# SCH_airPi_2024-02-11.net
KiCad netlist of a schematic drawn in EasyEDA
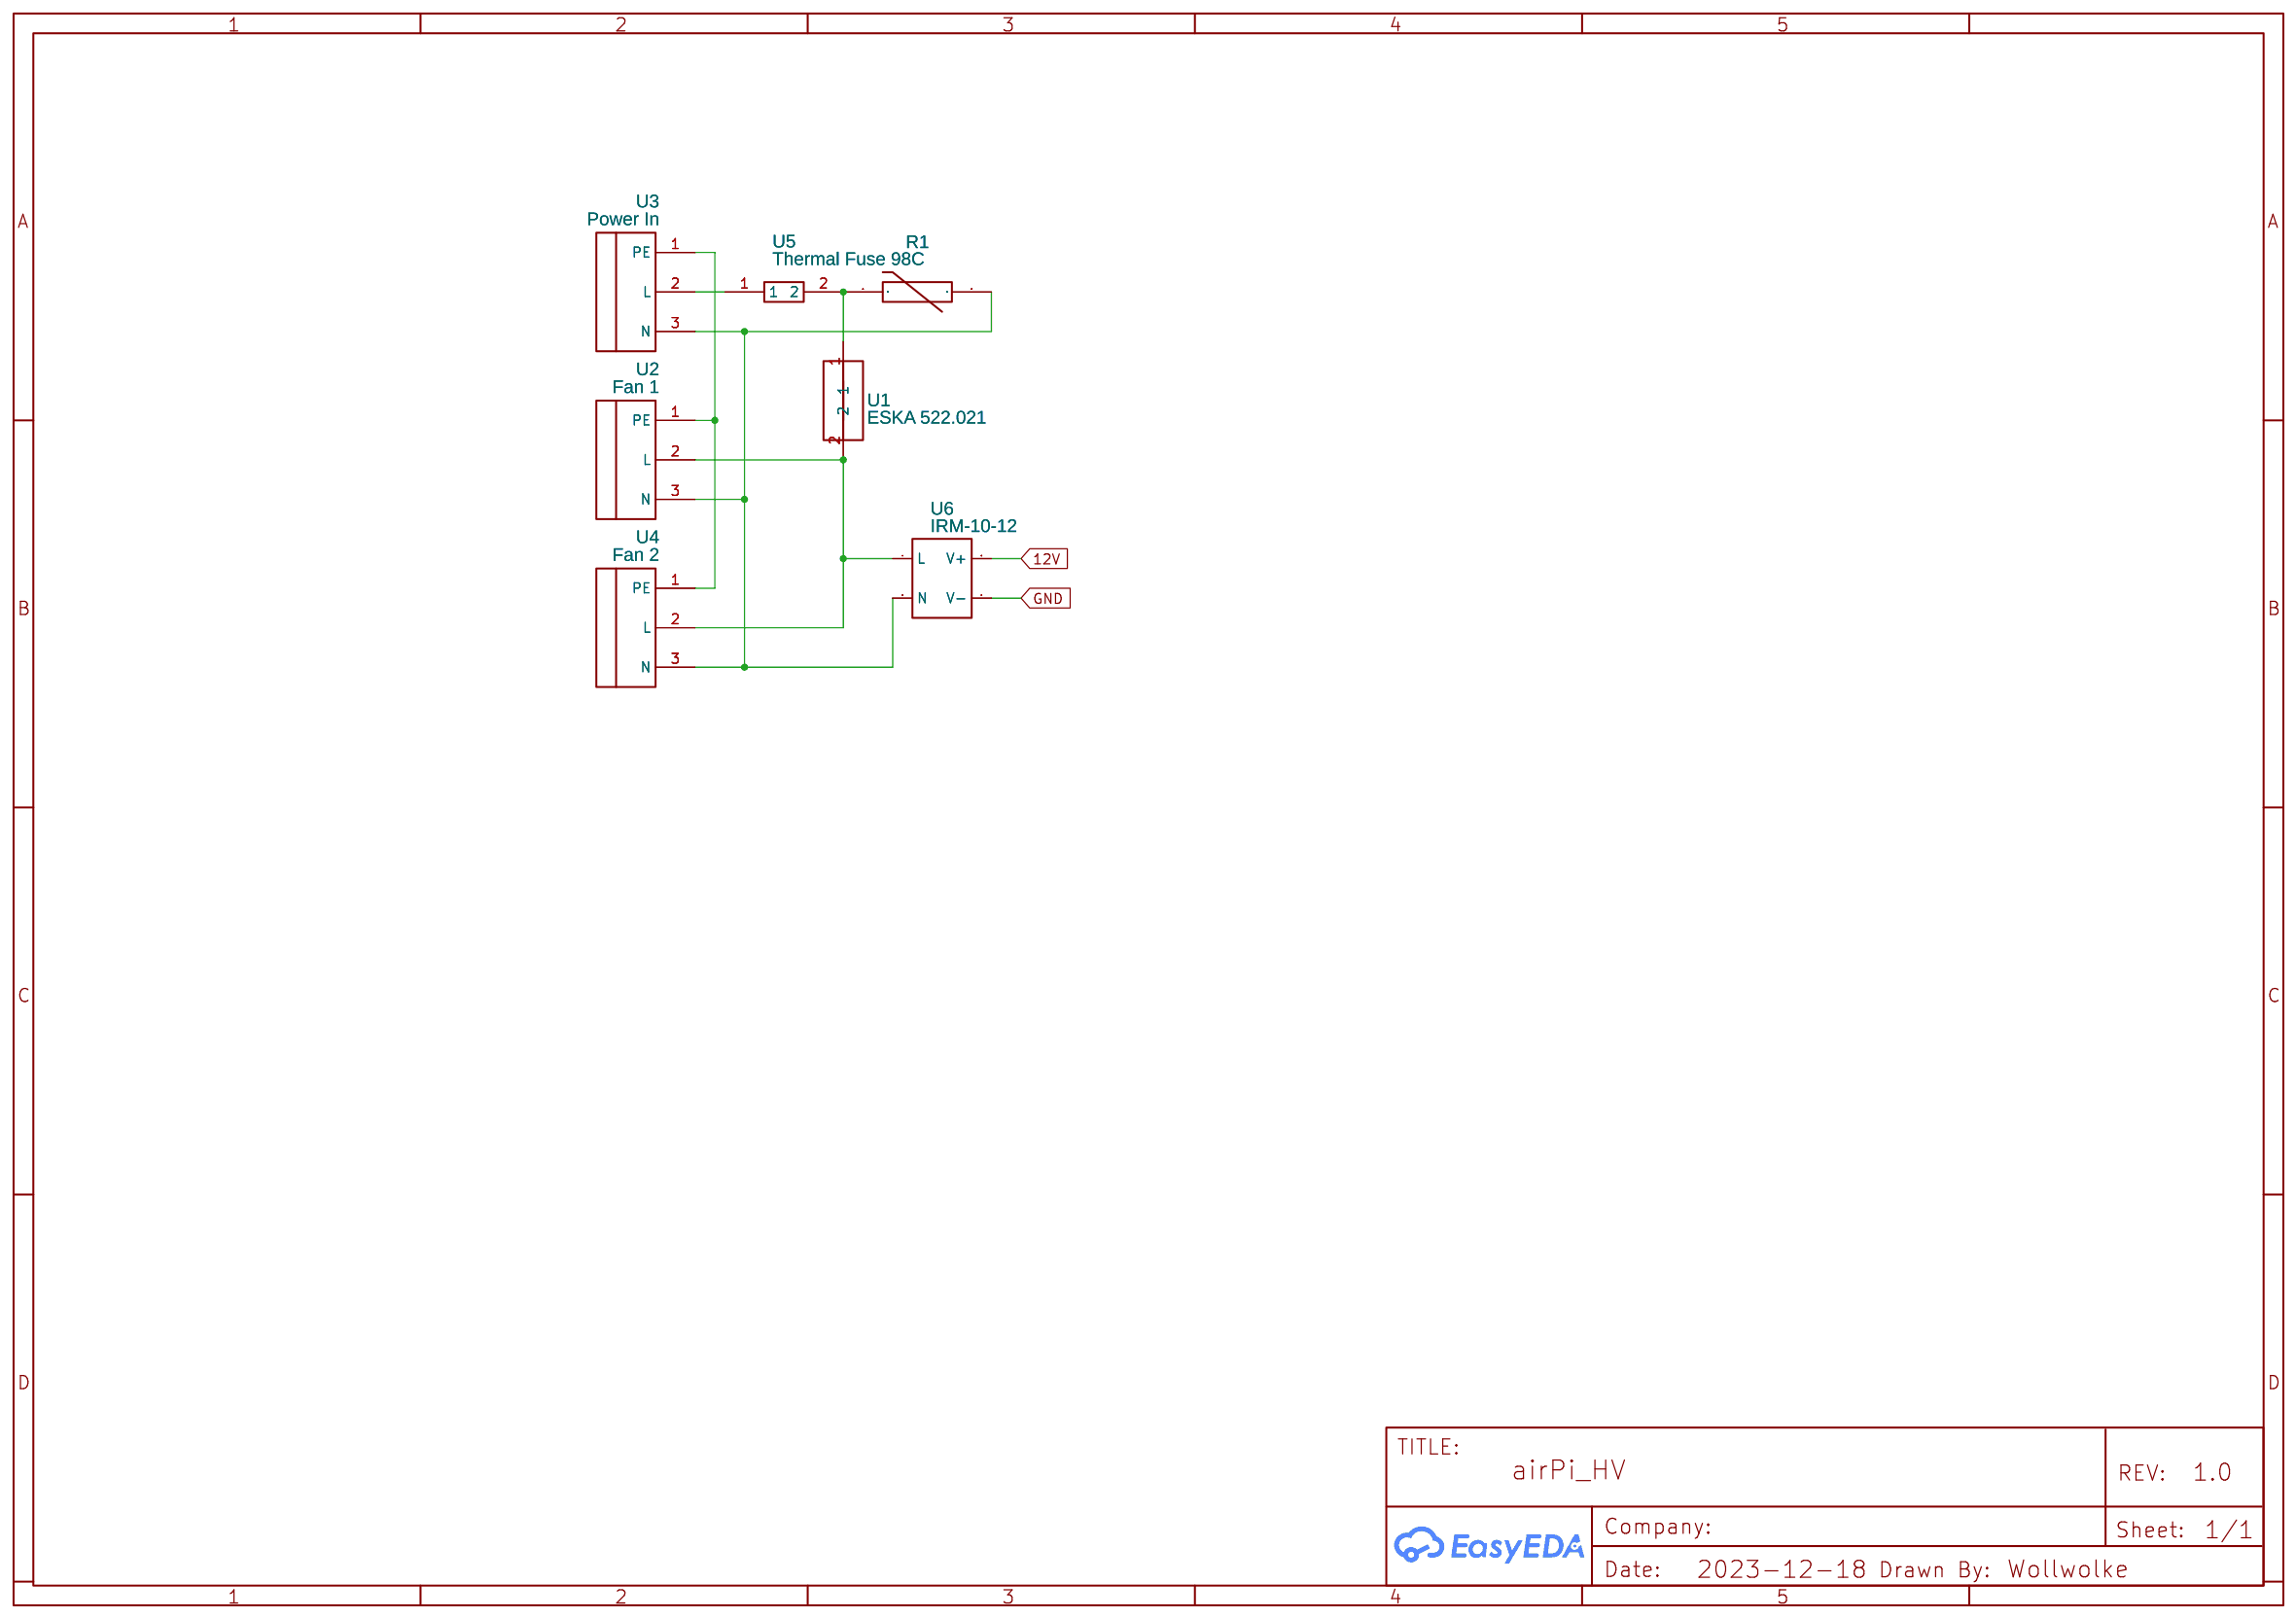
[diagram p0: airPi_HV]
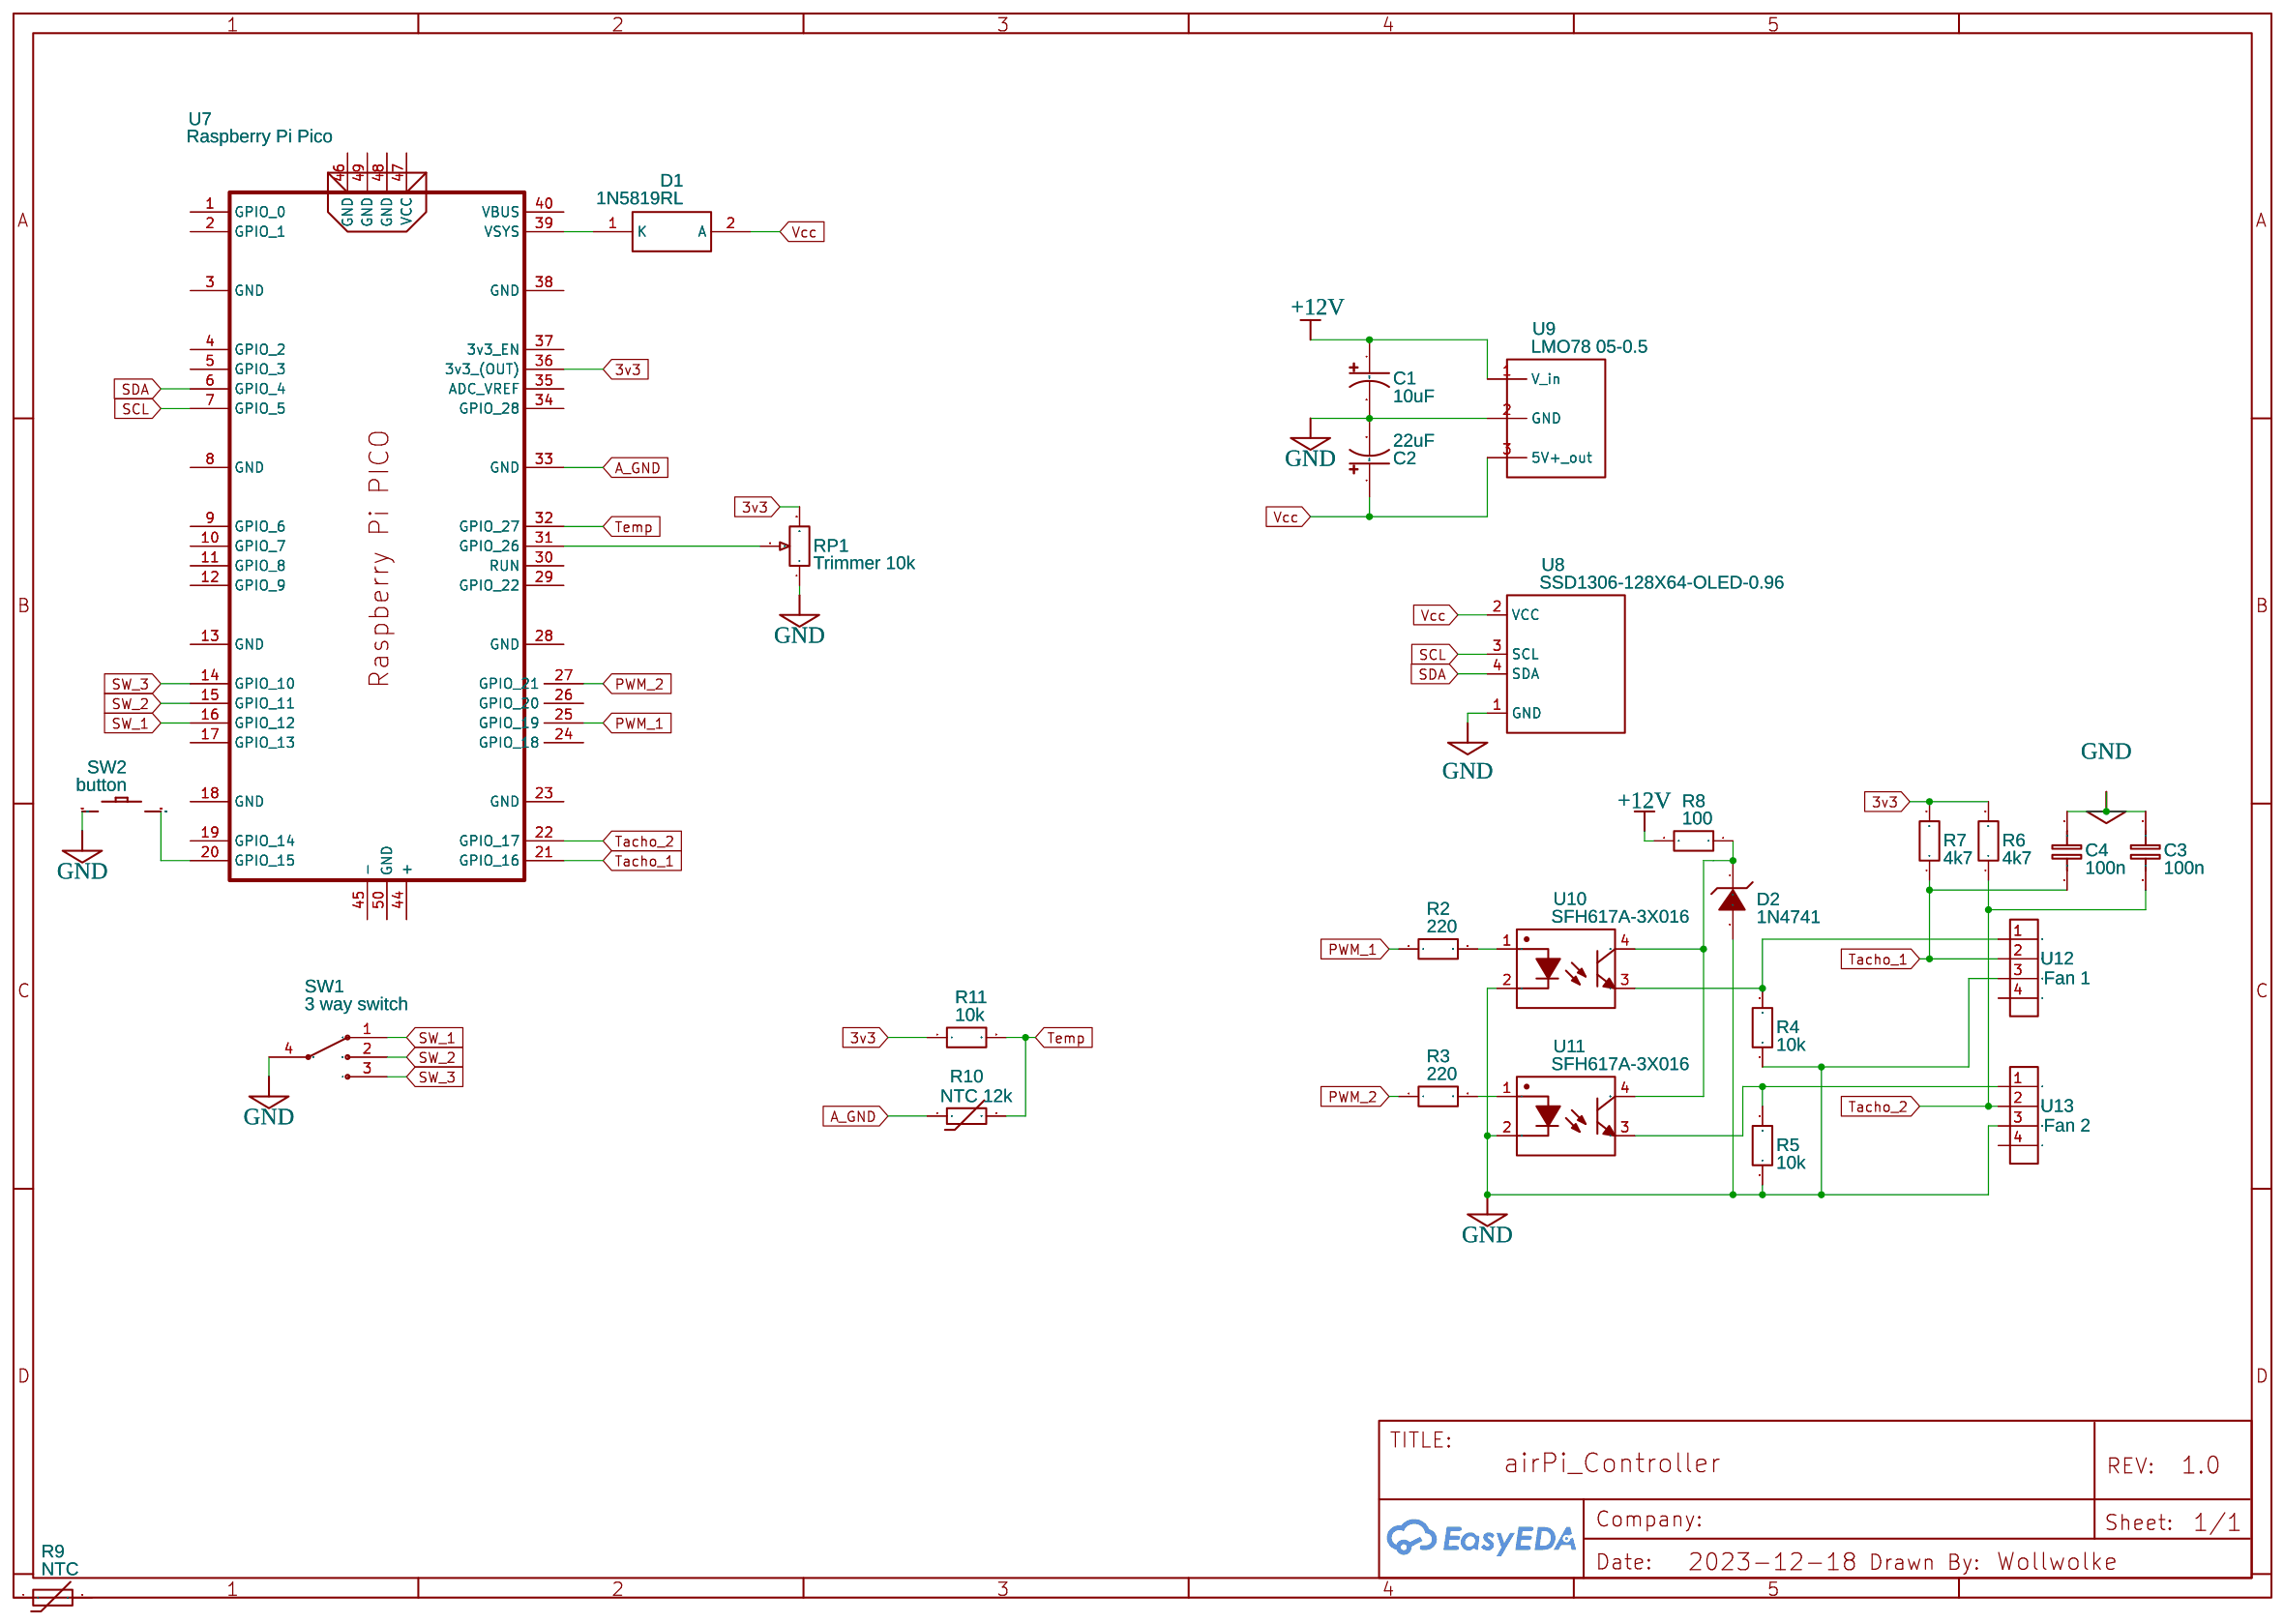
[diagram p1: airPi_Controller]

(export (version "E")
  (design (tool "Eeschema 10.0.6"))
  (components
    (comp (ref "R1")
      (value "Varistor")
      (fields
        (field (name "Manufacturer Part") "B72220S0301K101")
        (field (name "Manufacturer") "EPCOS - TDK Electronics")
      )
      (libsource (lib "") (part "B72220S0301K551"))
    )
    (comp (ref "U1")
      (value "ESKA 522.021")
      (fields (field (name "Manufacturer Part") "2050000172717"))
      (libsource (lib "") (part "ESKA 380"))
    )
    (comp (ref "U2")
      (value "Fan 1")
      (fields
        (field (name "Manufacturer Part") "MSTBA 2,5/ 3-G-5,08")
        (field (name "Manufacturer") "Phoenix Contact(菲尼克斯)")
      )
      (libsource (lib "") (part "MSTBA 2,5/ 3-G-5,08"))
    )
    (comp (ref "U3")
      (value "Power In")
      (fields
        (field (name "Manufacturer Part") "MSTBA 2,5/ 3-G-5,08")
        (field (name "Manufacturer") "Phoenix Contact(菲尼克斯)")
      )
      (libsource (lib "") (part "MSTBA 2,5/ 3-G-5,08"))
    )
    (comp (ref "U4")
      (value "Fan 2")
      (fields
        (field (name "Manufacturer Part") "MSTBA 2,5/ 3-G-5,08")
        (field (name "Manufacturer") "Phoenix Contact(菲尼克斯)")
      )
      (libsource (lib "") (part "MSTBA 2,5/ 3-G-5,08"))
    )
    (comp (ref "U5")
      (value "Thermal Fuse 98C")
      (fields (field (name "Manufacturer Part") "777.098") (field (name "Manufacturer") "ESKA"))
      (libsource (lib "") (part "Thermal Fuse ESKA"))
    )
    (comp (ref "U6")
      (value "IRM-10-12")
      (fields (field (name "Manufacturer") "MEAN WELL USA Inc."))
      (libsource (lib "") (part "IRM-10-12"))
    )
    (comp (ref "C1") (value "10uF") (libsource (lib "") (part "TANTALE-10µF")))
    (comp (ref "C2") (value "22uF") (libsource (lib "") (part "TANTALE-10µF_1")))
    (comp (ref "C3") (value "100n") (libsource (lib "") (part "C_0603_EU")))
    (comp (ref "C4") (value "100n") (libsource (lib "") (part "C_0603_EU")))
    (comp (ref "D1") (value "1N5819RL") (libsource (lib "") (part "1N5819RL")))
    (comp (ref "D2")
      (value "1N4741")
      (fields (field (name "Manufacturer Part") "1N4741A") (field (name "Manufacturer") "onsemi(安森美)"))
      (libsource (lib "") (part "1N4741A_C238927"))
    )
    (comp (ref "R2") (value "220") (libsource (lib "") (part "R_0603_EU_1")))
    (comp (ref "R3") (value "220") (libsource (lib "") (part "R_0603_EU_1")))
    (comp (ref "R4") (value "10k") (libsource (lib "") (part "R_0603_EU")))
    (comp (ref "R5") (value "10k") (libsource (lib "") (part "R_0603_EU")))
    (comp (ref "R6") (value "4k7") (libsource (lib "") (part "R_0603_EU")))
    (comp (ref "R7") (value "4k7") (libsource (lib "") (part "R_0603_EU")))
    (comp (ref "R8") (value "100") (libsource (lib "") (part "R_0603_EU_2")))
    (comp (ref "R9")
      (value "NTC")
      (fields (field (name "Manufacturer Part") "NTC 5D-9(弯脚)") (field (name "Manufacturer") "RUILON(瑞隆源)"))
      (libsource (lib "") (part "NTC 5D-9"))
    )
    (comp (ref "R10")
      (value "NTC 12k")
      (fields (field (name "Manufacturer Part") "NTC 5D-9(弯脚)") (field (name "Manufacturer") "RUILON(瑞隆源)"))
      (libsource (lib "") (part "NTC 5D-9"))
    )
    (comp (ref "R11") (value "10k") (libsource (lib "") (part "R_0603_EU_1")))
    (comp (ref "RP1") (value "Trimmer 10k") (libsource (lib "") (part "R_3386P_EU")))
    (comp (ref "SW1")
      (value "3 way switch")
      (fields
        (field (name "Manufacturer Part") "MSK-11027 Toggle Switches")
        (field (name "Manufacturer") "ReliaPro")
      )
      (libsource (lib "") (part "3 way switch"))
    )
    (comp (ref "SW2") (value "button") (libsource (lib "") (part "button")))
    (comp (ref "U7") (value "Raspberry Pi Pico") (libsource (lib "") (part "Raspberry Pi Pico")))
    (comp (ref "U8")
      (value "SSD1306-128X64-OLED-0.96")
      (libsource (lib "") (part "SSD1306-128X64-OLED-0.96"))
    )
    (comp (ref "U9")
      (value "LMO78 05-0.5")
      (libsource (lib "") (part "5V DC/DC Converter Gaptec LMO78 05-0.5 2,5W"))
    )
    (comp (ref "U10")
      (value "SFH617A-3X016")
      (fields (field (name "Manufacturer") "VISHAY(威世)"))
      (libsource (lib "") (part "SFH617A-3X016"))
    )
    (comp (ref "U11")
      (value "SFH617A-3X016")
      (fields (field (name "Manufacturer") "VISHAY(威世)"))
      (libsource (lib "") (part "SFH617A-3X016"))
    )
    (comp (ref "U12") (value "Fan 1") (libsource (lib "") (part "MolexMiniFit Jr 02*02")))
    (comp (ref "U13") (value "Fan 2") (libsource (lib "") (part "MolexMiniFit Jr 02*02")))
  )
  (nets
    (net (code "1") (name "+12V") (class "Default")
      (node (ref "C1") (pin "1") (pinfunction "1_1") (pintype "unspecified"))
      (node (ref "R8") (pin "2") (pinfunction "2_2") (pintype "unspecified"))
      (node (ref "U9") (pin "1") (pinfunction "V_in_1") (pintype "unspecified"))
    )
    (net (code "2") (name "3v3") (class "Default")
      (node (ref "R11") (pin "1") (pinfunction "1_1") (pintype "unspecified"))
      (node (ref "R6") (pin "2") (pinfunction "2_2") (pintype "unspecified"))
      (node (ref "R7") (pin "2") (pinfunction "2_2") (pintype "unspecified"))
      (node (ref "RP1") (pin "3") (pinfunction "3_3") (pintype "input"))
      (node (ref "U7") (pin "36") (pinfunction "3v3_(OUT)_36") (pintype "unspecified"))
    )
    (net (code "3") (name "12V") (class "Default")
      (node (ref "U6") (pin "V+") (pinfunction "V+_V+") (pintype "unspecified"))
    )
    (net (code "4") (name "A_GND") (class "Default")
      (node (ref "R10") (pin "1") (pinfunction "1_1") (pintype "input"))
      (node (ref "U7") (pin "33") (pinfunction "GND_33") (pintype "unspecified"))
    )
    (net (code "5") (name "GND") (class "Default")
      (node (ref "C1") (pin "2") (pinfunction "2_2") (pintype "unspecified"))
      (node (ref "C2") (pin "2") (pinfunction "2_2") (pintype "unspecified"))
      (node (ref "C3") (pin "2") (pinfunction "2_2") (pintype "unspecified"))
      (node (ref "C4") (pin "2") (pinfunction "2_2") (pintype "unspecified"))
      (node (ref "D2") (pin "2") (pinfunction "A_2") (pintype "unspecified"))
      (node (ref "R4") (pin "1") (pinfunction "1_1") (pintype "unspecified"))
      (node (ref "R5") (pin "1") (pinfunction "1_1") (pintype "unspecified"))
      (node (ref "RP1") (pin "1") (pinfunction "1_1") (pintype "input"))
      (node (ref "SW1") (pin "4") (pinfunction "2_4") (pintype "unspecified"))
      (node (ref "SW2") (pin "P$ACTIVE") (pinfunction "P$ACTIVE_P$ACTIVE") (pintype "unspecified"))
      (node (ref "U10") (pin "2") (pinfunction "C_2") (pintype "unspecified"))
      (node (ref "U11") (pin "2") (pinfunction "C_2") (pintype "unspecified"))
      (node (ref "U12") (pin "3") (pinfunction "3_3") (pintype "unspecified"))
      (node (ref "U13") (pin "3") (pinfunction "3_3") (pintype "unspecified"))
      (node (ref "U6") (pin "V-") (pinfunction "V-_V-") (pintype "unspecified"))
      (node (ref "U8") (pin "1") (pinfunction "GND_1") (pintype "input"))
      (node (ref "U9") (pin "2") (pinfunction "GND_2") (pintype "unspecified"))
    )
    (net (code "6") (name "Net-(D1-K)") (class "Default")
      (node (ref "D1") (pin "1") (pinfunction "K_1") (pintype "unspecified"))
      (node (ref "U7") (pin "39") (pinfunction "VSYS_39") (pintype "unspecified"))
    )
    (net (code "7") (name "Net-(D2-K)") (class "Default")
      (node (ref "D2") (pin "1") (pinfunction "K_1") (pintype "unspecified"))
      (node (ref "R8") (pin "1") (pinfunction "1_1") (pintype "unspecified"))
      (node (ref "U10") (pin "4") (pinfunction "C_4") (pintype "unspecified"))
      (node (ref "U11") (pin "4") (pinfunction "C_4") (pintype "unspecified"))
    )
    (net (code "8") (name "Net-(R1-Pad2)") (class "Default")
      (node (ref "R1") (pin "2") (pinfunction "2_2") (pintype "unspecified"))
      (node (ref "U1") (pin "1") (pinfunction "1_1") (pintype "unspecified"))
      (node (ref "U5") (pin "2") (pinfunction "2_2") (pintype "unspecified"))
    )
    (net (code "9") (name "Net-(U2-L)") (class "Default")
      (node (ref "U1") (pin "2") (pinfunction "2_2") (pintype "unspecified"))
      (node (ref "U2") (pin "2") (pinfunction "L_2") (pintype "unspecified"))
      (node (ref "U4") (pin "2") (pinfunction "L_2") (pintype "unspecified"))
      (node (ref "U6") (pin "L") (pinfunction "L_L") (pintype "unspecified"))
    )
    (net (code "10") (name "Net-(U2-N)") (class "Default")
      (node (ref "R1") (pin "1") (pinfunction "1_1") (pintype "unspecified"))
      (node (ref "U2") (pin "3") (pinfunction "N_3") (pintype "unspecified"))
      (node (ref "U3") (pin "3") (pinfunction "N_3") (pintype "unspecified"))
      (node (ref "U4") (pin "3") (pinfunction "N_3") (pintype "unspecified"))
      (node (ref "U6") (pin "N") (pinfunction "N_N") (pintype "unspecified"))
    )
    (net (code "11") (name "Net-(U2-PE)") (class "Default")
      (node (ref "U2") (pin "1") (pinfunction "PE_1") (pintype "unspecified"))
      (node (ref "U3") (pin "1") (pinfunction "PE_1") (pintype "unspecified"))
      (node (ref "U4") (pin "1") (pinfunction "PE_1") (pintype "unspecified"))
    )
    (net (code "12") (name "Net-(U3-L)") (class "Default")
      (node (ref "U3") (pin "2") (pinfunction "L_2") (pintype "unspecified"))
      (node (ref "U5") (pin "1") (pinfunction "1_1") (pintype "unspecified"))
    )
    (net (code "13") (name "Net-(U7-GPIO_15)") (class "Default")
      (node (ref "SW2") (pin "P$GND") (pinfunction "P$GND_P$GND") (pintype "unspecified"))
      (node (ref "U7") (pin "20") (pinfunction "GPIO_15_20") (pintype "unspecified"))
    )
    (net (code "14") (name "Net-(U7-GPIO_26)") (class "Default")
      (node (ref "RP1") (pin "2") (pinfunction "2_2") (pintype "input"))
      (node (ref "U7") (pin "31") (pinfunction "GPIO_26_31") (pintype "unspecified"))
    )
    (net (code "15") (name "Net-(U10-A)") (class "Default")
      (node (ref "R2") (pin "2") (pinfunction "2_2") (pintype "unspecified"))
      (node (ref "U10") (pin "1") (pinfunction "A_1") (pintype "unspecified"))
    )
    (net (code "16") (name "Net-(U10-E)") (class "Default")
      (node (ref "R4") (pin "2") (pinfunction "2_2") (pintype "unspecified"))
      (node (ref "U10") (pin "3") (pinfunction "E_3") (pintype "unspecified"))
      (node (ref "U12") (pin "1") (pinfunction "1_1") (pintype "unspecified"))
    )
    (net (code "17") (name "Net-(U11-A)") (class "Default")
      (node (ref "R3") (pin "2") (pinfunction "2_2") (pintype "unspecified"))
      (node (ref "U11") (pin "1") (pinfunction "A_1") (pintype "unspecified"))
    )
    (net (code "18") (name "Net-(U11-E)") (class "Default")
      (node (ref "R5") (pin "2") (pinfunction "2_2") (pintype "unspecified"))
      (node (ref "U11") (pin "3") (pinfunction "E_3") (pintype "unspecified"))
      (node (ref "U13") (pin "1") (pinfunction "1_1") (pintype "unspecified"))
    )
    (net (code "19") (name "PWM_1") (class "Default")
      (node (ref "R2") (pin "1") (pinfunction "1_1") (pintype "unspecified"))
      (node (ref "U7") (pin "25") (pinfunction "GPIO_19_25") (pintype "unspecified"))
    )
    (net (code "20") (name "PWM_2") (class "Default")
      (node (ref "R3") (pin "1") (pinfunction "1_1") (pintype "unspecified"))
      (node (ref "U7") (pin "27") (pinfunction "GPIO_21_27") (pintype "unspecified"))
    )
    (net (code "21") (name "SCL") (class "Default")
      (node (ref "U7") (pin "7") (pinfunction "GPIO_5_7") (pintype "unspecified"))
      (node (ref "U8") (pin "3") (pinfunction "SCL_3") (pintype "passive"))
    )
    (net (code "22") (name "SDA") (class "Default")
      (node (ref "U7") (pin "6") (pinfunction "GPIO_4_6") (pintype "unspecified"))
      (node (ref "U8") (pin "4") (pinfunction "SDA_4") (pintype "passive"))
    )
    (net (code "23") (name "SW_1") (class "Default")
      (node (ref "SW1") (pin "1") (pinfunction "1_1") (pintype "unspecified"))
      (node (ref "U7") (pin "16") (pinfunction "GPIO_12_16") (pintype "unspecified"))
    )
    (net (code "24") (name "SW_2") (class "Default")
      (node (ref "SW1") (pin "2") (pinfunction "3_2") (pintype "unspecified"))
      (node (ref "U7") (pin "15") (pinfunction "GPIO_11_15") (pintype "unspecified"))
    )
    (net (code "25") (name "SW_3") (class "Default")
      (node (ref "SW1") (pin "3") (pinfunction "4_3") (pintype "unspecified"))
      (node (ref "U7") (pin "14") (pinfunction "GPIO_10_14") (pintype "unspecified"))
    )
    (net (code "26") (name "Tacho_1") (class "Default")
      (node (ref "C4") (pin "1") (pinfunction "1_1") (pintype "unspecified"))
      (node (ref "R7") (pin "1") (pinfunction "1_1") (pintype "unspecified"))
      (node (ref "U12") (pin "2") (pinfunction "2_2") (pintype "unspecified"))
      (node (ref "U7") (pin "21") (pinfunction "GPIO_16_21") (pintype "unspecified"))
    )
    (net (code "27") (name "Tacho_2") (class "Default")
      (node (ref "C3") (pin "1") (pinfunction "1_1") (pintype "unspecified"))
      (node (ref "R6") (pin "1") (pinfunction "1_1") (pintype "unspecified"))
      (node (ref "U13") (pin "2") (pinfunction "2_2") (pintype "unspecified"))
      (node (ref "U7") (pin "22") (pinfunction "GPIO_17_22") (pintype "unspecified"))
    )
    (net (code "28") (name "Temp") (class "Default")
      (node (ref "R10") (pin "2") (pinfunction "2_2") (pintype "input"))
      (node (ref "R11") (pin "2") (pinfunction "2_2") (pintype "unspecified"))
      (node (ref "U7") (pin "32") (pinfunction "GPIO_27_32") (pintype "unspecified"))
    )
    (net (code "29") (name "Vcc") (class "Default")
      (node (ref "C2") (pin "1") (pinfunction "1_1") (pintype "unspecified"))
      (node (ref "D1") (pin "2") (pinfunction "A_2") (pintype "unspecified"))
      (node (ref "U8") (pin "2") (pinfunction "VCC_2") (pintype "input"))
      (node (ref "U9") (pin "3") (pinfunction "5V+_out_3") (pintype "unspecified"))
    )
    (net (code "30") (name "unconnected-(R9-Pad1)") (class "Default")
      (node (ref "R9") (pin "1") (pinfunction "1_1") (pintype "input"))
    )
    (net (code "31") (name "unconnected-(R9-Pad2)") (class "Default")
      (node (ref "R9") (pin "2") (pinfunction "2_2") (pintype "input"))
    )
    (net (code "32") (name "unconnected-(U7-+-Pad44)") (class "Default")
      (node (ref "U7") (pin "44") (pinfunction "+_44") (pintype "passive"))
    )
    (net (code "33") (name "unconnected-(U7---Pad45)") (class "Default")
      (node (ref "U7") (pin "45") (pinfunction "-_45") (pintype "passive"))
    )
    (net (code "34") (name "unconnected-(U7-3v3_EN-Pad37)") (class "Default")
      (node (ref "U7") (pin "37") (pinfunction "3v3_EN_37") (pintype "unspecified"))
    )
    (net (code "35") (name "unconnected-(U7-ADC_VREF-Pad35)") (class "Default")
      (node (ref "U7") (pin "35") (pinfunction "ADC_VREF_35") (pintype "unspecified"))
    )
    (net (code "36") (name "unconnected-(U7-GND-Pad3)") (class "Default")
      (node (ref "U7") (pin "3") (pinfunction "GND_3") (pintype "unspecified"))
    )
    (net (code "37") (name "unconnected-(U7-GND-Pad8)") (class "Default")
      (node (ref "U7") (pin "8") (pinfunction "GND_8") (pintype "unspecified"))
    )
    (net (code "38") (name "unconnected-(U7-GND-Pad13)") (class "Default")
      (node (ref "U7") (pin "13") (pinfunction "GND_13") (pintype "unspecified"))
    )
    (net (code "39") (name "unconnected-(U7-GND-Pad18)") (class "Default")
      (node (ref "U7") (pin "18") (pinfunction "GND_18") (pintype "unspecified"))
    )
    (net (code "40") (name "unconnected-(U7-GND-Pad23)") (class "Default")
      (node (ref "U7") (pin "23") (pinfunction "GND_23") (pintype "unspecified"))
    )
    (net (code "41") (name "unconnected-(U7-GND-Pad28)") (class "Default")
      (node (ref "U7") (pin "28") (pinfunction "GND_28") (pintype "unspecified"))
    )
    (net (code "42") (name "unconnected-(U7-GND-Pad38)") (class "Default")
      (node (ref "U7") (pin "38") (pinfunction "GND_38") (pintype "unspecified"))
    )
    (net (code "43") (name "unconnected-(U7-GND-Pad46)") (class "Default")
      (node (ref "U7") (pin "46") (pinfunction "GND_46") (pintype "unspecified"))
    )
    (net (code "44") (name "unconnected-(U7-GND-Pad48)") (class "Default")
      (node (ref "U7") (pin "48") (pinfunction "GND_48") (pintype "unspecified"))
    )
    (net (code "45") (name "unconnected-(U7-GND-Pad49)") (class "Default")
      (node (ref "U7") (pin "49") (pinfunction "GND_49") (pintype "unspecified"))
    )
    (net (code "46") (name "unconnected-(U7-GND-Pad50)") (class "Default")
      (node (ref "U7") (pin "50") (pinfunction "GND_50") (pintype "unspecified"))
    )
    (net (code "47") (name "unconnected-(U7-GPIO_0-Pad1)") (class "Default")
      (node (ref "U7") (pin "1") (pinfunction "GPIO_0_1") (pintype "unspecified"))
    )
    (net (code "48") (name "unconnected-(U7-GPIO_1-Pad2)") (class "Default")
      (node (ref "U7") (pin "2") (pinfunction "GPIO_1_2") (pintype "unspecified"))
    )
    (net (code "49") (name "unconnected-(U7-GPIO_2-Pad4)") (class "Default")
      (node (ref "U7") (pin "4") (pinfunction "GPIO_2_4") (pintype "unspecified"))
    )
    (net (code "50") (name "unconnected-(U7-GPIO_3-Pad5)") (class "Default")
      (node (ref "U7") (pin "5") (pinfunction "GPIO_3_5") (pintype "unspecified"))
    )
    (net (code "51") (name "unconnected-(U7-GPIO_6-Pad9)") (class "Default")
      (node (ref "U7") (pin "9") (pinfunction "GPIO_6_9") (pintype "unspecified"))
    )
    (net (code "52") (name "unconnected-(U7-GPIO_7-Pad10)") (class "Default")
      (node (ref "U7") (pin "10") (pinfunction "GPIO_7_10") (pintype "unspecified"))
    )
    (net (code "53") (name "unconnected-(U7-GPIO_8-Pad11)") (class "Default")
      (node (ref "U7") (pin "11") (pinfunction "GPIO_8_11") (pintype "unspecified"))
    )
    (net (code "54") (name "unconnected-(U7-GPIO_9-Pad12)") (class "Default")
      (node (ref "U7") (pin "12") (pinfunction "GPIO_9_12") (pintype "unspecified"))
    )
    (net (code "55") (name "unconnected-(U7-GPIO_13-Pad17)") (class "Default")
      (node (ref "U7") (pin "17") (pinfunction "GPIO_13_17") (pintype "unspecified"))
    )
    (net (code "56") (name "unconnected-(U7-GPIO_14-Pad19)") (class "Default")
      (node (ref "U7") (pin "19") (pinfunction "GPIO_14_19") (pintype "unspecified"))
    )
    (net (code "57") (name "unconnected-(U7-GPIO_18-Pad24)") (class "Default")
      (node (ref "U7") (pin "24") (pinfunction "GPIO_18_24") (pintype "unspecified"))
    )
    (net (code "58") (name "unconnected-(U7-GPIO_20-Pad26)") (class "Default")
      (node (ref "U7") (pin "26") (pinfunction "GPIO_20_26") (pintype "unspecified"))
    )
    (net (code "59") (name "unconnected-(U7-GPIO_22-Pad29)") (class "Default")
      (node (ref "U7") (pin "29") (pinfunction "GPIO_22_29") (pintype "unspecified"))
    )
    (net (code "60") (name "unconnected-(U7-GPIO_28-Pad34)") (class "Default")
      (node (ref "U7") (pin "34") (pinfunction "GPIO_28_34") (pintype "unspecified"))
    )
    (net (code "61") (name "unconnected-(U7-RUN-Pad30)") (class "Default")
      (node (ref "U7") (pin "30") (pinfunction "RUN_30") (pintype "unspecified"))
    )
    (net (code "62") (name "unconnected-(U7-VBUS-Pad40)") (class "Default")
      (node (ref "U7") (pin "40") (pinfunction "VBUS_40") (pintype "unspecified"))
    )
    (net (code "63") (name "unconnected-(U7-VCC-Pad47)") (class "Default")
      (node (ref "U7") (pin "47") (pinfunction "VCC_47") (pintype "unspecified"))
    )
    (net (code "64") (name "unconnected-(U12-Pad4)") (class "Default")
      (node (ref "U12") (pin "4") (pinfunction "4_4") (pintype "unspecified"))
    )
    (net (code "65") (name "unconnected-(U13-Pad4)") (class "Default")
      (node (ref "U13") (pin "4") (pinfunction "4_4") (pintype "unspecified"))
    )
  )
)
